# AddMixShift.net
KiCad netlist of a schematic drawn in EAGLE
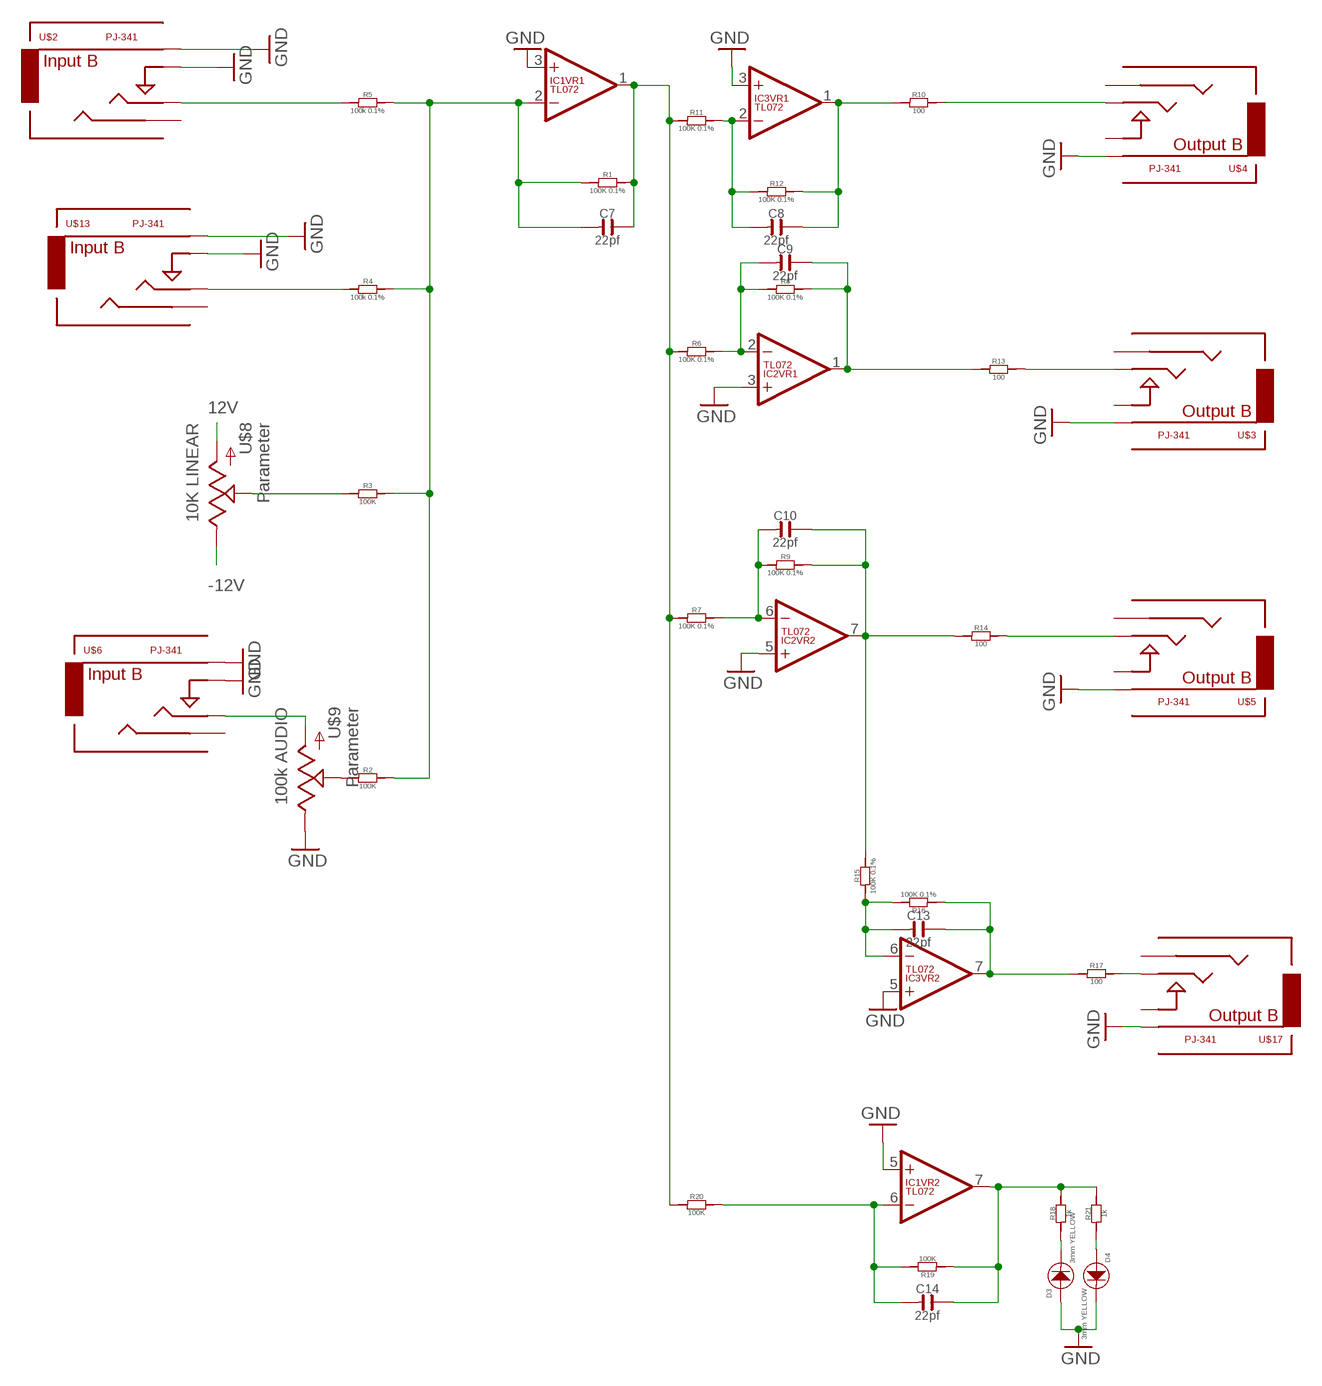
[diagram p0: schematic, sheet 1, part 1 of 2]
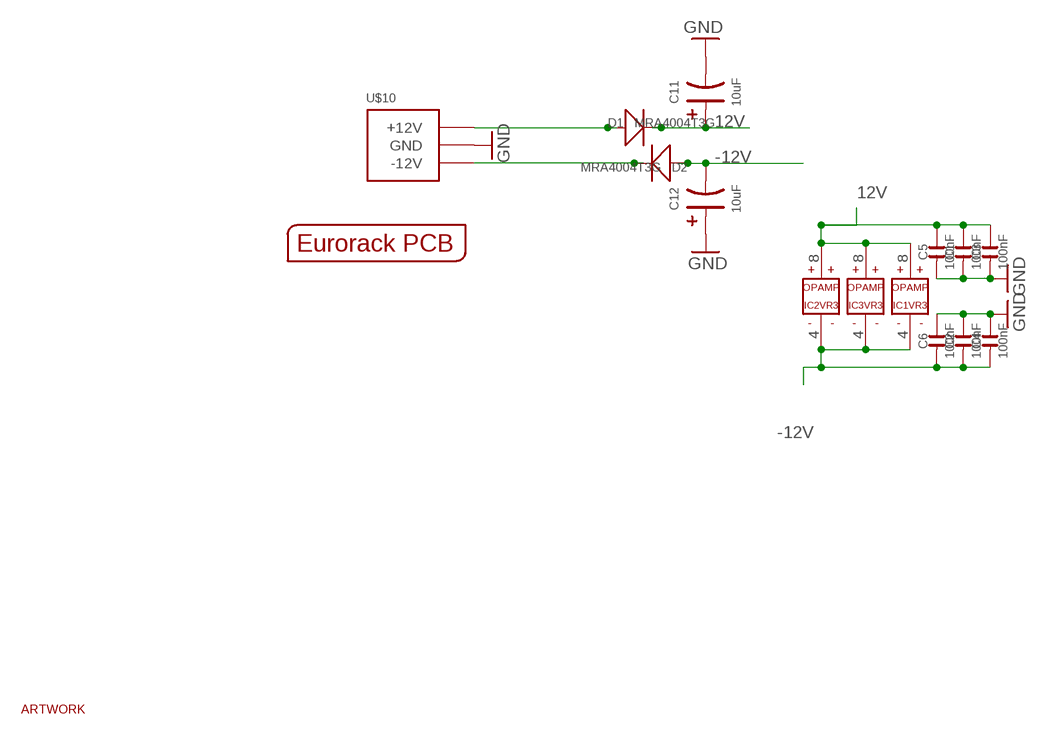
[diagram p1: schematic, sheet 1, part 2 of 2]

(export (version "E")
  (design (tool "Eeschema 10.0.6"))
  (components
    (comp (ref "C1")
      (value "100nF")
      (footprint "eagle-import:C0603")
      (libsource (lib "eagle-import") (part "C-0603"))
    )
    (comp (ref "C2")
      (value "100nF")
      (footprint "eagle-import:C0603")
      (libsource (lib "eagle-import") (part "C-0603"))
    )
    (comp (ref "C3")
      (value "100nF")
      (footprint "eagle-import:C0603")
      (libsource (lib "eagle-import") (part "C-0603"))
    )
    (comp (ref "C4")
      (value "100nF")
      (footprint "eagle-import:C0603")
      (libsource (lib "eagle-import") (part "C-0603"))
    )
    (comp (ref "C5")
      (value "100nF")
      (footprint "eagle-import:C0603")
      (libsource (lib "eagle-import") (part "C-0603"))
    )
    (comp (ref "C6")
      (value "100nF")
      (footprint "eagle-import:C0603")
      (libsource (lib "eagle-import") (part "C-0603"))
    )
    (comp (ref "C7")
      (value "22pf")
      (footprint "eagle-import:C0603")
      (libsource (lib "eagle-import") (part "C-0603"))
    )
    (comp (ref "C8")
      (value "22pf")
      (footprint "eagle-import:C0603")
      (libsource (lib "eagle-import") (part "C-0603"))
    )
    (comp (ref "C9")
      (value "22pf")
      (footprint "eagle-import:C0603")
      (libsource (lib "eagle-import") (part "C-0603"))
    )
    (comp (ref "C10")
      (value "22pf")
      (footprint "eagle-import:C0603")
      (libsource (lib "eagle-import") (part "C-0603"))
    )
    (comp (ref "C11")
      (value "10uF")
      (footprint "eagle-import:AVX-A")
      (libsource (lib "eagle-import") (part "C-POLAR-A"))
    )
    (comp (ref "C12")
      (value "10uF")
      (footprint "eagle-import:AVX-A")
      (libsource (lib "eagle-import") (part "C-POLAR-A"))
    )
    (comp (ref "C13")
      (value "22pf")
      (footprint "eagle-import:C0603")
      (libsource (lib "eagle-import") (part "C-0603"))
    )
    (comp (ref "C14")
      (value "22pf")
      (footprint "eagle-import:C0603")
      (libsource (lib "eagle-import") (part "C-0603"))
    )
    (comp (ref "D1")
      (value "MRA4004T3G")
      (footprint "eagle-import:DO-214AC")
      (fields (field (name "MF") "VISHAY") (field (name "MPN") "US1G-E3/5AT"))
      (libsource (lib "eagle-import") (part "D-SMA"))
    )
    (comp (ref "D2")
      (value "MRA4004T3G")
      (footprint "eagle-import:DO-214AC")
      (fields (field (name "MF") "VISHAY") (field (name "MPN") "US1G-E3/5AT"))
      (libsource (lib "eagle-import") (part "D-SMA"))
    )
    (comp (ref "D3")
      (value "3mm YELLOW")
      (footprint "eagle-import:3MMLED")
      (libsource (lib "eagle-import") (part "LED3MM"))
    )
    (comp (ref "D4")
      (value "3mm YELLOW")
      (footprint "eagle-import:3MMLED")
      (libsource (lib "eagle-import") (part "LED3MM"))
    )
    (comp (ref "IC1")
      (value "TL072")
      (footprint "eagle-import:SO08")
      (libsource (lib "eagle-import") (part "TL072"))
    )
    (comp (ref "IC2")
      (value "TL072")
      (footprint "eagle-import:SO08")
      (libsource (lib "eagle-import") (part "TL072"))
    )
    (comp (ref "IC3")
      (value "TL072")
      (footprint "eagle-import:SO08")
      (libsource (lib "eagle-import") (part "TL072"))
    )
    (comp (ref "R1")
      (value "100K 0.1%")
      (footprint "eagle-import:R0603")
      (libsource (lib "eagle-import") (part "R-0603"))
    )
    (comp (ref "R2")
      (value "100K")
      (footprint "eagle-import:R0603")
      (libsource (lib "eagle-import") (part "R-0603"))
    )
    (comp (ref "R3")
      (value "100K")
      (footprint "eagle-import:R0603")
      (libsource (lib "eagle-import") (part "R-0603"))
    )
    (comp (ref "R4")
      (value "100k 0.1%")
      (footprint "eagle-import:R0603")
      (libsource (lib "eagle-import") (part "R-0603"))
    )
    (comp (ref "R5")
      (value "100k 0.1%")
      (footprint "eagle-import:R0603")
      (libsource (lib "eagle-import") (part "R-0603"))
    )
    (comp (ref "R6")
      (value "100K 0.1%")
      (footprint "eagle-import:R0603")
      (libsource (lib "eagle-import") (part "R-0603"))
    )
    (comp (ref "R7")
      (value "100K 0.1%")
      (footprint "eagle-import:R0603")
      (libsource (lib "eagle-import") (part "R-0603"))
    )
    (comp (ref "R8")
      (value "100K 0.1%")
      (footprint "eagle-import:R0603")
      (libsource (lib "eagle-import") (part "R-0603"))
    )
    (comp (ref "R9")
      (value "100K 0.1%")
      (footprint "eagle-import:R0603")
      (libsource (lib "eagle-import") (part "R-0603"))
    )
    (comp (ref "R10")
      (value "100")
      (footprint "eagle-import:R0603")
      (libsource (lib "eagle-import") (part "R-0603"))
    )
    (comp (ref "R11")
      (value "100K 0.1%")
      (footprint "eagle-import:R0603")
      (libsource (lib "eagle-import") (part "R-0603"))
    )
    (comp (ref "R12")
      (value "100K 0.1%")
      (footprint "eagle-import:R0603")
      (libsource (lib "eagle-import") (part "R-0603"))
    )
    (comp (ref "R13")
      (value "100")
      (footprint "eagle-import:R0603")
      (libsource (lib "eagle-import") (part "R-0603"))
    )
    (comp (ref "R14")
      (value "100")
      (footprint "eagle-import:R0603")
      (libsource (lib "eagle-import") (part "R-0603"))
    )
    (comp (ref "R15")
      (value "100K 0.1%")
      (footprint "eagle-import:R0603")
      (libsource (lib "eagle-import") (part "R-0603"))
    )
    (comp (ref "R16")
      (value "100K 0.1%")
      (footprint "eagle-import:R0603")
      (libsource (lib "eagle-import") (part "R-0603"))
    )
    (comp (ref "R17")
      (value "100")
      (footprint "eagle-import:R0603")
      (libsource (lib "eagle-import") (part "R-0603"))
    )
    (comp (ref "R18")
      (value "1k")
      (footprint "eagle-import:R0603")
      (libsource (lib "eagle-import") (part "R-0603"))
    )
    (comp (ref "R19")
      (value "100K")
      (footprint "eagle-import:R0603")
      (libsource (lib "eagle-import") (part "R-0603"))
    )
    (comp (ref "R20")
      (value "100K")
      (footprint "eagle-import:R0603")
      (libsource (lib "eagle-import") (part "R-0603"))
    )
    (comp (ref "R21")
      (value "1k")
      (footprint "eagle-import:R0603")
      (libsource (lib "eagle-import") (part "R-0603"))
    )
    (comp (ref "U$1")
      (value "EURORACK_PCB4HP")
      (footprint "eagle-import:EURORACK4HPPCB")
      (libsource (lib "eagle-import") (part "EURORACK_PCB4HP"))
    )
    (comp (ref "U$2")
      (value "PJ-341")
      (footprint "eagle-import:3.5MM-JACK-SWITCH-13MM-INPUT")
      (fields (field (name "DESC") "Input B"))
      (libsource (lib "eagle-import") (part "AUDIO-JACKINPUT"))
    )
    (comp (ref "U$3")
      (value "PJ-341")
      (footprint "eagle-import:3.5MM-JACK-SWITCH-13MM-OUTPUT")
      (fields (field (name "DESC") "Output B"))
      (libsource (lib "eagle-import") (part "AUDIO-JACKOUTPUT"))
    )
    (comp (ref "U$4")
      (value "PJ-341")
      (footprint "eagle-import:3.5MM-JACK-SWITCH-13MM-OUTPUT")
      (fields (field (name "DESC") "Output B"))
      (libsource (lib "eagle-import") (part "AUDIO-JACKOUTPUT"))
    )
    (comp (ref "U$5")
      (value "PJ-341")
      (footprint "eagle-import:3.5MM-JACK-SWITCH-13MM-OUTPUT")
      (fields (field (name "DESC") "Output B"))
      (libsource (lib "eagle-import") (part "AUDIO-JACKOUTPUT"))
    )
    (comp (ref "U$6")
      (value "PJ-341")
      (footprint "eagle-import:3.5MM-JACK-SWITCH-13MM-INPUT")
      (fields (field (name "DESC") "Input B"))
      (libsource (lib "eagle-import") (part "AUDIO-JACKINPUT"))
    )
    (comp (ref "U$8")
      (value "10K LINEAR")
      (footprint "eagle-import:OG-POTS_ALPS_POT_VERTICAL")
      (libsource (lib "eagle-import") (part "POTZEPHPOT"))
    )
    (comp (ref "U$9")
      (value "100k AUDIO")
      (footprint "eagle-import:OG-POTS_ALPS_POT_VERTICAL")
      (libsource (lib "eagle-import") (part "POTZEPHPOT"))
    )
    (comp (ref "U$10")
      (value "POWER_SIMPLE")
      (footprint "eagle-import:2X05_SMT_HEADER")
      (libsource (lib "eagle-import") (part "POWER_SIMPLE"))
    )
    (comp (ref "U$11")
      (value "TINRS_ARTWORKROCKET")
      (footprint "eagle-import:TINRS_ROCKET")
      (libsource (lib "eagle-import") (part "TINRS_ARTWORKROCKET"))
    )
    (comp (ref "U$13")
      (value "PJ-341")
      (footprint "eagle-import:3.5MM-JACK-SWITCH-13MM-INPUT")
      (fields (field (name "DESC") "Input B"))
      (libsource (lib "eagle-import") (part "AUDIO-JACKINPUT"))
    )
    (comp (ref "U$17")
      (value "PJ-341")
      (footprint "eagle-import:3.5MM-JACK-SWITCH-13MM-OUTPUT")
      (fields (field (name "DESC") "Output B"))
      (libsource (lib "eagle-import") (part "AUDIO-JACKOUTPUT"))
    )
  )
  (nets
    (net (code "1") (name "/-12V") (class "Default")
      (node (ref "C12") (pin "-") (pinfunction "2_-") (pintype "bidirectional"))
      (node (ref "C2") (pin "1") (pinfunction "1_1") (pintype "bidirectional"))
      (node (ref "C4") (pin "1") (pinfunction "1_1") (pintype "bidirectional"))
      (node (ref "C6") (pin "1") (pinfunction "1_1") (pintype "bidirectional"))
      (node (ref "D2") (pin "1") (pinfunction "+_1") (pintype "passive"))
      (node (ref "IC1") (pin "4") (pinfunction "V-_4") (pintype "power_in"))
      (node (ref "IC2") (pin "4") (pinfunction "V-_4") (pintype "power_in"))
      (node (ref "IC3") (pin "4") (pinfunction "V-_4") (pintype "power_in"))
      (node (ref "U$8") (pin "P$1") (pinfunction "E_P$1") (pintype "passive"))
    )
    (net (code "2") (name "/12V") (class "Default")
      (node (ref "C1") (pin "2") (pinfunction "2_2") (pintype "bidirectional"))
      (node (ref "C11") (pin "+") (pinfunction "1_+") (pintype "bidirectional"))
      (node (ref "C3") (pin "2") (pinfunction "2_2") (pintype "bidirectional"))
      (node (ref "C5") (pin "2") (pinfunction "2_2") (pintype "bidirectional"))
      (node (ref "D1") (pin "2") (pinfunction "-_2") (pintype "passive"))
      (node (ref "IC1") (pin "8") (pinfunction "V+_8") (pintype "power_in"))
      (node (ref "IC2") (pin "8") (pinfunction "V+_8") (pintype "power_in"))
      (node (ref "IC3") (pin "8") (pinfunction "V+_8") (pintype "power_in"))
      (node (ref "U$8") (pin "P$3") (pinfunction "A_P$3") (pintype "passive"))
    )
    (net (code "3") (name "GND") (class "Default")
      (node (ref "C1") (pin "1") (pinfunction "1_1") (pintype "bidirectional"))
      (node (ref "C11") (pin "-") (pinfunction "2_-") (pintype "bidirectional"))
      (node (ref "C12") (pin "+") (pinfunction "1_+") (pintype "bidirectional"))
      (node (ref "C2") (pin "2") (pinfunction "2_2") (pintype "bidirectional"))
      (node (ref "C3") (pin "1") (pinfunction "1_1") (pintype "bidirectional"))
      (node (ref "C4") (pin "2") (pinfunction "2_2") (pintype "bidirectional"))
      (node (ref "C5") (pin "1") (pinfunction "1_1") (pintype "bidirectional"))
      (node (ref "C6") (pin "2") (pinfunction "2_2") (pintype "bidirectional"))
      (node (ref "D3") (pin "+") (pinfunction "+_+") (pintype "passive"))
      (node (ref "D4") (pin "-") (pinfunction "-_-") (pintype "passive"))
      (node (ref "IC1") (pin "3") (pinfunction "+IN_3") (pintype "input"))
      (node (ref "IC1") (pin "5") (pinfunction "+IN_5") (pintype "input"))
      (node (ref "IC2") (pin "3") (pinfunction "+IN_3") (pintype "input"))
      (node (ref "IC2") (pin "5") (pinfunction "+IN_5") (pintype "input"))
      (node (ref "IC3") (pin "3") (pinfunction "+IN_3") (pintype "input"))
      (node (ref "IC3") (pin "5") (pinfunction "+IN_5") (pintype "input"))
      (node (ref "U$10") (pin "3") (pinfunction "GND_3") (pintype "bidirectional"))
      (node (ref "U$10") (pin "4") (pinfunction "GND_4") (pintype "bidirectional"))
      (node (ref "U$10") (pin "5") (pinfunction "GND_5") (pintype "bidirectional"))
      (node (ref "U$10") (pin "6") (pinfunction "GND_6") (pintype "bidirectional"))
      (node (ref "U$10") (pin "7") (pinfunction "GND_7") (pintype "bidirectional"))
      (node (ref "U$10") (pin "8") (pinfunction "GND_8") (pintype "bidirectional"))
      (node (ref "U$13") (pin "RING@3") (pinfunction "RING_RING@3") (pintype "bidirectional"))
      (node (ref "U$13") (pin "SWITCH@3") (pinfunction "SWITCH_SWITCH@3") (pintype "bidirectional"))
      (node (ref "U$17") (pin "RING@3") (pinfunction "RING_RING@3") (pintype "bidirectional"))
      (node (ref "U$2") (pin "RING@3") (pinfunction "RING_RING@3") (pintype "bidirectional"))
      (node (ref "U$2") (pin "SWITCH@3") (pinfunction "SWITCH_SWITCH@3") (pintype "bidirectional"))
      (node (ref "U$3") (pin "RING@3") (pinfunction "RING_RING@3") (pintype "bidirectional"))
      (node (ref "U$4") (pin "RING@3") (pinfunction "RING_RING@3") (pintype "bidirectional"))
      (node (ref "U$5") (pin "RING@3") (pinfunction "RING_RING@3") (pintype "bidirectional"))
      (node (ref "U$6") (pin "RING@3") (pinfunction "RING_RING@3") (pintype "bidirectional"))
      (node (ref "U$6") (pin "SWITCH@3") (pinfunction "SWITCH_SWITCH@3") (pintype "bidirectional"))
      (node (ref "U$9") (pin "P$1") (pinfunction "E_P$1") (pintype "passive"))
    )
    (net (code "4") (name "Net-(D1-+)") (class "Default")
      (node (ref "D1") (pin "1") (pinfunction "+_1") (pintype "passive"))
      (node (ref "U$10") (pin "10") (pinfunction "+12V_10") (pintype "bidirectional"))
      (node (ref "U$10") (pin "9") (pinfunction "+12V_9") (pintype "bidirectional"))
    )
    (net (code "5") (name "Net-(D2--)") (class "Default")
      (node (ref "D2") (pin "2") (pinfunction "-_2") (pintype "passive"))
      (node (ref "U$10") (pin "1") (pinfunction "-12V_1") (pintype "bidirectional"))
      (node (ref "U$10") (pin "2") (pinfunction "-12V_2") (pintype "bidirectional"))
    )
    (net (code "6") (name "Net-(D3-Pad-)") (class "Default")
      (node (ref "D3") (pin "-") (pinfunction "-_-") (pintype "passive"))
      (node (ref "R18") (pin "1") (pinfunction "1_1") (pintype "bidirectional"))
    )
    (net (code "7") (name "Net-(D4-Pad+)") (class "Default")
      (node (ref "D4") (pin "+") (pinfunction "+_+") (pintype "passive"))
      (node (ref "R21") (pin "1") (pinfunction "1_1") (pintype "bidirectional"))
    )
    (net (code "8") (name "Net-(IC1A--IN)") (class "Default")
      (node (ref "C7") (pin "1") (pinfunction "1_1") (pintype "bidirectional"))
      (node (ref "IC1") (pin "2") (pinfunction "-IN_2") (pintype "input"))
      (node (ref "R1") (pin "1") (pinfunction "1_1") (pintype "bidirectional"))
      (node (ref "R2") (pin "2") (pinfunction "2_2") (pintype "bidirectional"))
      (node (ref "R3") (pin "2") (pinfunction "2_2") (pintype "bidirectional"))
      (node (ref "R4") (pin "2") (pinfunction "2_2") (pintype "bidirectional"))
      (node (ref "R5") (pin "2") (pinfunction "2_2") (pintype "bidirectional"))
    )
    (net (code "9") (name "Net-(IC1A-OUT)") (class "Default")
      (node (ref "C7") (pin "2") (pinfunction "2_2") (pintype "bidirectional"))
      (node (ref "IC1") (pin "1") (pinfunction "OUT_1") (pintype "output"))
      (node (ref "R1") (pin "2") (pinfunction "2_2") (pintype "bidirectional"))
      (node (ref "R11") (pin "1") (pinfunction "1_1") (pintype "bidirectional"))
      (node (ref "R20") (pin "1") (pinfunction "1_1") (pintype "bidirectional"))
      (node (ref "R6") (pin "1") (pinfunction "1_1") (pintype "bidirectional"))
      (node (ref "R7") (pin "1") (pinfunction "1_1") (pintype "bidirectional"))
    )
    (net (code "10") (name "Net-(IC1B--IN)") (class "Default")
      (node (ref "C14") (pin "1") (pinfunction "1_1") (pintype "bidirectional"))
      (node (ref "IC1") (pin "6") (pinfunction "-IN_6") (pintype "input"))
      (node (ref "R19") (pin "2") (pinfunction "2_2") (pintype "bidirectional"))
      (node (ref "R20") (pin "2") (pinfunction "2_2") (pintype "bidirectional"))
    )
    (net (code "11") (name "Net-(IC1B-OUT)") (class "Default")
      (node (ref "C14") (pin "2") (pinfunction "2_2") (pintype "bidirectional"))
      (node (ref "IC1") (pin "7") (pinfunction "OUT_7") (pintype "output"))
      (node (ref "R18") (pin "2") (pinfunction "2_2") (pintype "bidirectional"))
      (node (ref "R19") (pin "1") (pinfunction "1_1") (pintype "bidirectional"))
      (node (ref "R21") (pin "2") (pinfunction "2_2") (pintype "bidirectional"))
    )
    (net (code "12") (name "Net-(IC2A--IN)") (class "Default")
      (node (ref "C9") (pin "1") (pinfunction "1_1") (pintype "bidirectional"))
      (node (ref "IC2") (pin "2") (pinfunction "-IN_2") (pintype "input"))
      (node (ref "R6") (pin "2") (pinfunction "2_2") (pintype "bidirectional"))
      (node (ref "R8") (pin "1") (pinfunction "1_1") (pintype "bidirectional"))
    )
    (net (code "13") (name "Net-(IC2A-OUT)") (class "Default")
      (node (ref "C9") (pin "2") (pinfunction "2_2") (pintype "bidirectional"))
      (node (ref "IC2") (pin "1") (pinfunction "OUT_1") (pintype "output"))
      (node (ref "R13") (pin "1") (pinfunction "1_1") (pintype "bidirectional"))
      (node (ref "R8") (pin "2") (pinfunction "2_2") (pintype "bidirectional"))
    )
    (net (code "14") (name "Net-(IC2B--IN)") (class "Default")
      (node (ref "C10") (pin "1") (pinfunction "1_1") (pintype "bidirectional"))
      (node (ref "IC2") (pin "6") (pinfunction "-IN_6") (pintype "input"))
      (node (ref "R7") (pin "2") (pinfunction "2_2") (pintype "bidirectional"))
      (node (ref "R9") (pin "1") (pinfunction "1_1") (pintype "bidirectional"))
    )
    (net (code "15") (name "Net-(IC2B-OUT)") (class "Default")
      (node (ref "C10") (pin "2") (pinfunction "2_2") (pintype "bidirectional"))
      (node (ref "IC2") (pin "7") (pinfunction "OUT_7") (pintype "output"))
      (node (ref "R14") (pin "1") (pinfunction "1_1") (pintype "bidirectional"))
      (node (ref "R15") (pin "2") (pinfunction "2_2") (pintype "bidirectional"))
      (node (ref "R9") (pin "2") (pinfunction "2_2") (pintype "bidirectional"))
    )
    (net (code "16") (name "Net-(IC3A--IN)") (class "Default")
      (node (ref "C8") (pin "1") (pinfunction "1_1") (pintype "bidirectional"))
      (node (ref "IC3") (pin "2") (pinfunction "-IN_2") (pintype "input"))
      (node (ref "R11") (pin "2") (pinfunction "2_2") (pintype "bidirectional"))
      (node (ref "R12") (pin "1") (pinfunction "1_1") (pintype "bidirectional"))
    )
    (net (code "17") (name "Net-(IC3A-OUT)") (class "Default")
      (node (ref "C8") (pin "2") (pinfunction "2_2") (pintype "bidirectional"))
      (node (ref "IC3") (pin "1") (pinfunction "OUT_1") (pintype "output"))
      (node (ref "R10") (pin "1") (pinfunction "1_1") (pintype "bidirectional"))
      (node (ref "R12") (pin "2") (pinfunction "2_2") (pintype "bidirectional"))
    )
    (net (code "18") (name "Net-(IC3B--IN)") (class "Default")
      (node (ref "C13") (pin "1") (pinfunction "1_1") (pintype "bidirectional"))
      (node (ref "IC3") (pin "6") (pinfunction "-IN_6") (pintype "input"))
      (node (ref "R15") (pin "1") (pinfunction "1_1") (pintype "bidirectional"))
      (node (ref "R16") (pin "2") (pinfunction "2_2") (pintype "bidirectional"))
    )
    (net (code "19") (name "Net-(IC3B-OUT)") (class "Default")
      (node (ref "C13") (pin "2") (pinfunction "2_2") (pintype "bidirectional"))
      (node (ref "IC3") (pin "7") (pinfunction "OUT_7") (pintype "output"))
      (node (ref "R16") (pin "1") (pinfunction "1_1") (pintype "bidirectional"))
      (node (ref "R17") (pin "1") (pinfunction "1_1") (pintype "bidirectional"))
    )
    (net (code "20") (name "Net-(U$2-TIP)") (class "Default")
      (node (ref "R5") (pin "1") (pinfunction "1_1") (pintype "bidirectional"))
      (node (ref "U$2") (pin "TIP@3") (pinfunction "TIP_TIP@3") (pintype "bidirectional"))
    )
    (net (code "21") (name "Net-(U$3-TIP)") (class "Default")
      (node (ref "R13") (pin "2") (pinfunction "2_2") (pintype "bidirectional"))
      (node (ref "U$3") (pin "TIP@3") (pinfunction "TIP_TIP@3") (pintype "bidirectional"))
    )
    (net (code "22") (name "Net-(U$4-TIP)") (class "Default")
      (node (ref "R10") (pin "2") (pinfunction "2_2") (pintype "bidirectional"))
      (node (ref "U$4") (pin "TIP@3") (pinfunction "TIP_TIP@3") (pintype "bidirectional"))
    )
    (net (code "23") (name "Net-(U$5-TIP)") (class "Default")
      (node (ref "R14") (pin "2") (pinfunction "2_2") (pintype "bidirectional"))
      (node (ref "U$5") (pin "TIP@3") (pinfunction "TIP_TIP@3") (pintype "bidirectional"))
    )
    (net (code "24") (name "Net-(U$6-TIP)") (class "Default")
      (node (ref "U$6") (pin "TIP@3") (pinfunction "TIP_TIP@3") (pintype "bidirectional"))
      (node (ref "U$9") (pin "P$3") (pinfunction "A_P$3") (pintype "passive"))
    )
    (net (code "25") (name "Net-(U$8-S)") (class "Default")
      (node (ref "R3") (pin "1") (pinfunction "1_1") (pintype "bidirectional"))
      (node (ref "U$8") (pin "P$2") (pinfunction "S_P$2") (pintype "passive"))
    )
    (net (code "26") (name "Net-(U$9-S)") (class "Default")
      (node (ref "R2") (pin "1") (pinfunction "1_1") (pintype "bidirectional"))
      (node (ref "U$9") (pin "P$2") (pinfunction "S_P$2") (pintype "passive"))
    )
    (net (code "27") (name "Net-(U$13-TIP)") (class "Default")
      (node (ref "R4") (pin "1") (pinfunction "1_1") (pintype "bidirectional"))
      (node (ref "U$13") (pin "TIP@3") (pinfunction "TIP_TIP@3") (pintype "bidirectional"))
    )
    (net (code "28") (name "Net-(U$17-TIP)") (class "Default")
      (node (ref "R17") (pin "2") (pinfunction "2_2") (pintype "bidirectional"))
      (node (ref "U$17") (pin "TIP@3") (pinfunction "TIP_TIP@3") (pintype "bidirectional"))
    )
    (net (code "29") (name "unconnected-(U$2-SECOND-PadSECOND@3)") (class "Default")
      (node (ref "U$2") (pin "SECOND@3") (pinfunction "SECOND_SECOND@3") (pintype "bidirectional"))
    )
    (net (code "30") (name "unconnected-(U$3-SECOND-PadSECOND@3)") (class "Default")
      (node (ref "U$3") (pin "SECOND@3") (pinfunction "SECOND_SECOND@3") (pintype "bidirectional"))
    )
    (net (code "31") (name "unconnected-(U$3-SWITCH-PadSWITCH@3)") (class "Default")
      (node (ref "U$3") (pin "SWITCH@3") (pinfunction "SWITCH_SWITCH@3") (pintype "bidirectional"))
    )
    (net (code "32") (name "unconnected-(U$4-SECOND-PadSECOND@3)") (class "Default")
      (node (ref "U$4") (pin "SECOND@3") (pinfunction "SECOND_SECOND@3") (pintype "bidirectional"))
    )
    (net (code "33") (name "unconnected-(U$4-SWITCH-PadSWITCH@3)") (class "Default")
      (node (ref "U$4") (pin "SWITCH@3") (pinfunction "SWITCH_SWITCH@3") (pintype "bidirectional"))
    )
    (net (code "34") (name "unconnected-(U$5-SECOND-PadSECOND@3)") (class "Default")
      (node (ref "U$5") (pin "SECOND@3") (pinfunction "SECOND_SECOND@3") (pintype "bidirectional"))
    )
    (net (code "35") (name "unconnected-(U$5-SWITCH-PadSWITCH@3)") (class "Default")
      (node (ref "U$5") (pin "SWITCH@3") (pinfunction "SWITCH_SWITCH@3") (pintype "bidirectional"))
    )
    (net (code "36") (name "unconnected-(U$6-SECOND-PadSECOND@3)") (class "Default")
      (node (ref "U$6") (pin "SECOND@3") (pinfunction "SECOND_SECOND@3") (pintype "bidirectional"))
    )
    (net (code "37") (name "unconnected-(U$13-SECOND-PadSECOND@3)") (class "Default")
      (node (ref "U$13") (pin "SECOND@3") (pinfunction "SECOND_SECOND@3") (pintype "bidirectional"))
    )
    (net (code "38") (name "unconnected-(U$17-SECOND-PadSECOND@3)") (class "Default")
      (node (ref "U$17") (pin "SECOND@3") (pinfunction "SECOND_SECOND@3") (pintype "bidirectional"))
    )
    (net (code "39") (name "unconnected-(U$17-SWITCH-PadSWITCH@3)") (class "Default")
      (node (ref "U$17") (pin "SWITCH@3") (pinfunction "SWITCH_SWITCH@3") (pintype "bidirectional"))
    )
  )
)
